# controller_v6.net
KiCad netlist of a schematic drawn in EAGLE
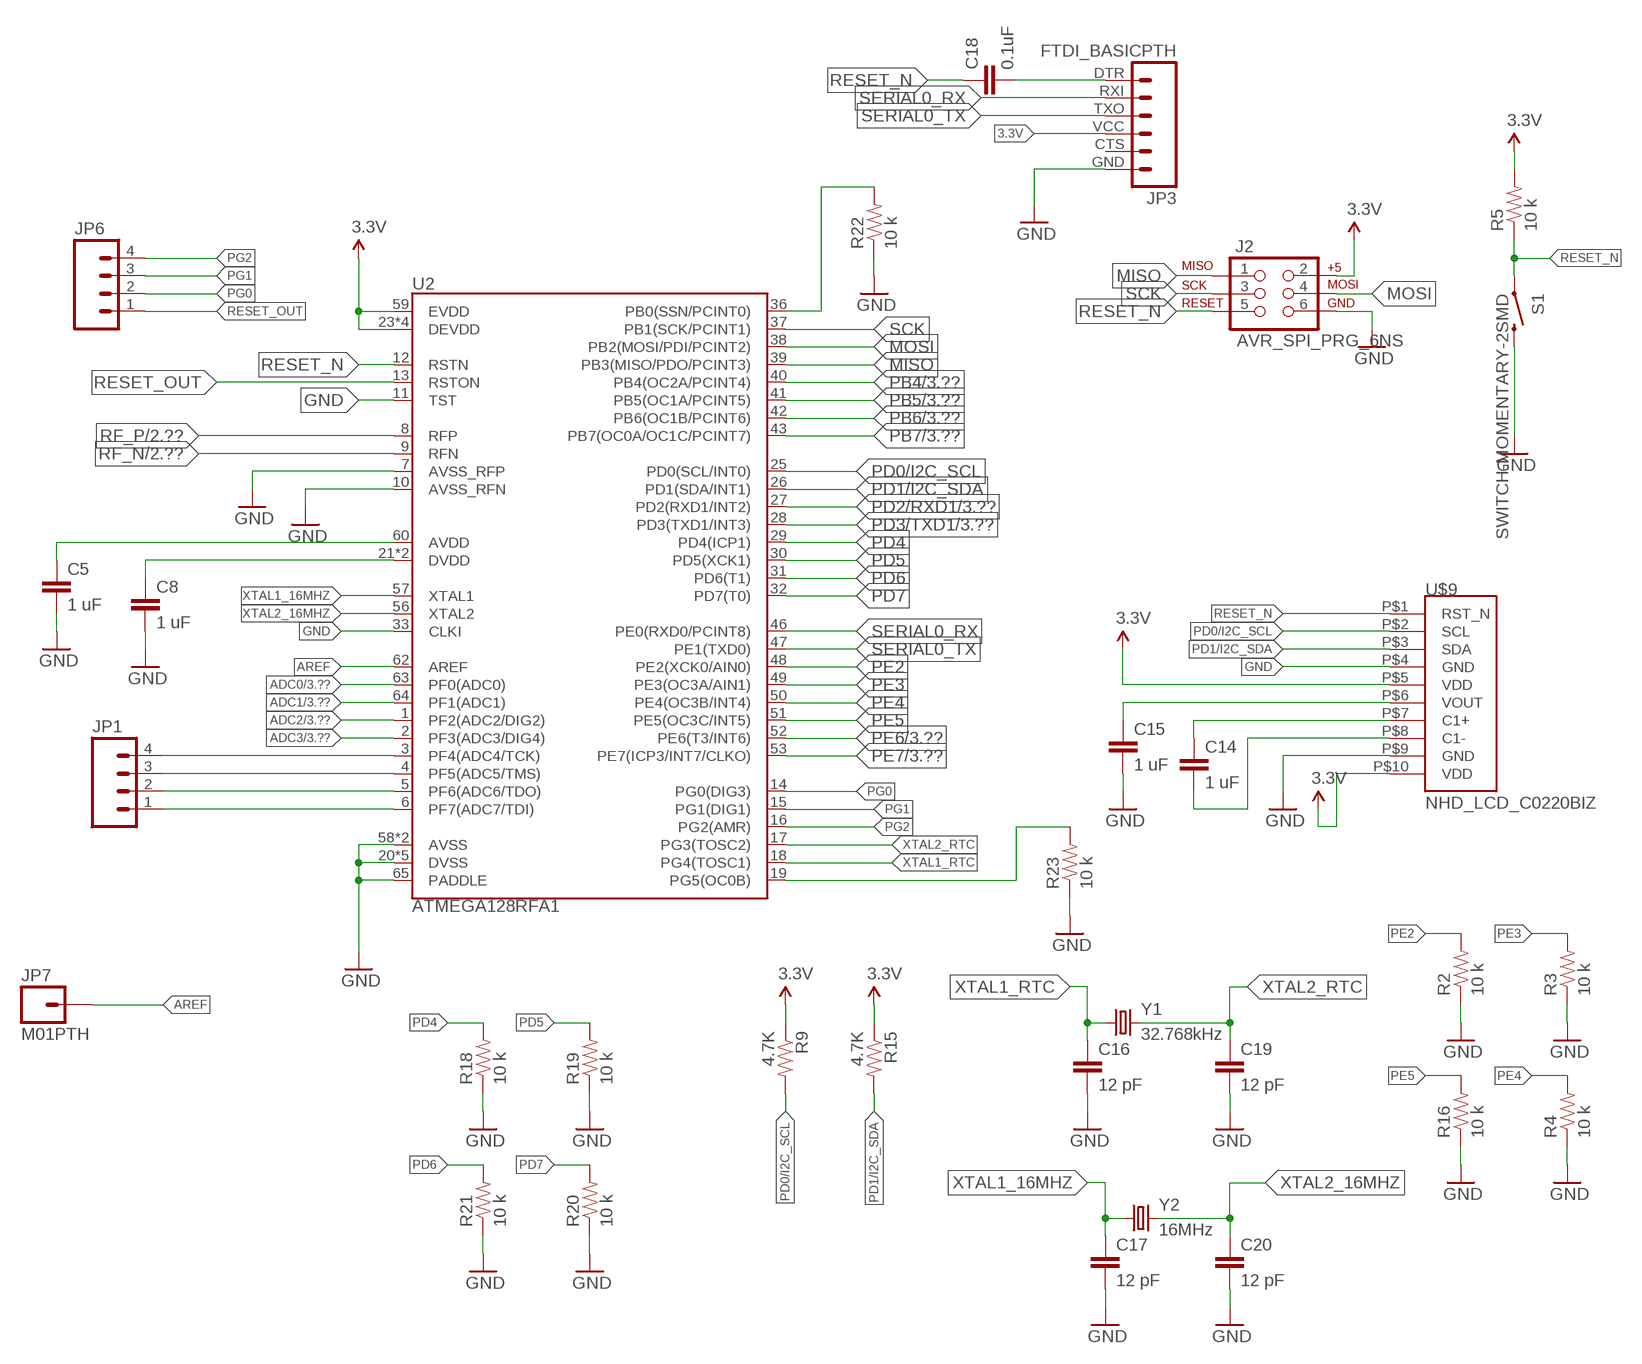
[diagram p0: schematic, sheet 1]
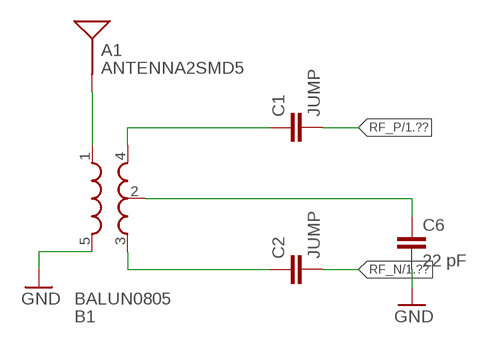
[diagram p1: schematic, sheet 2]
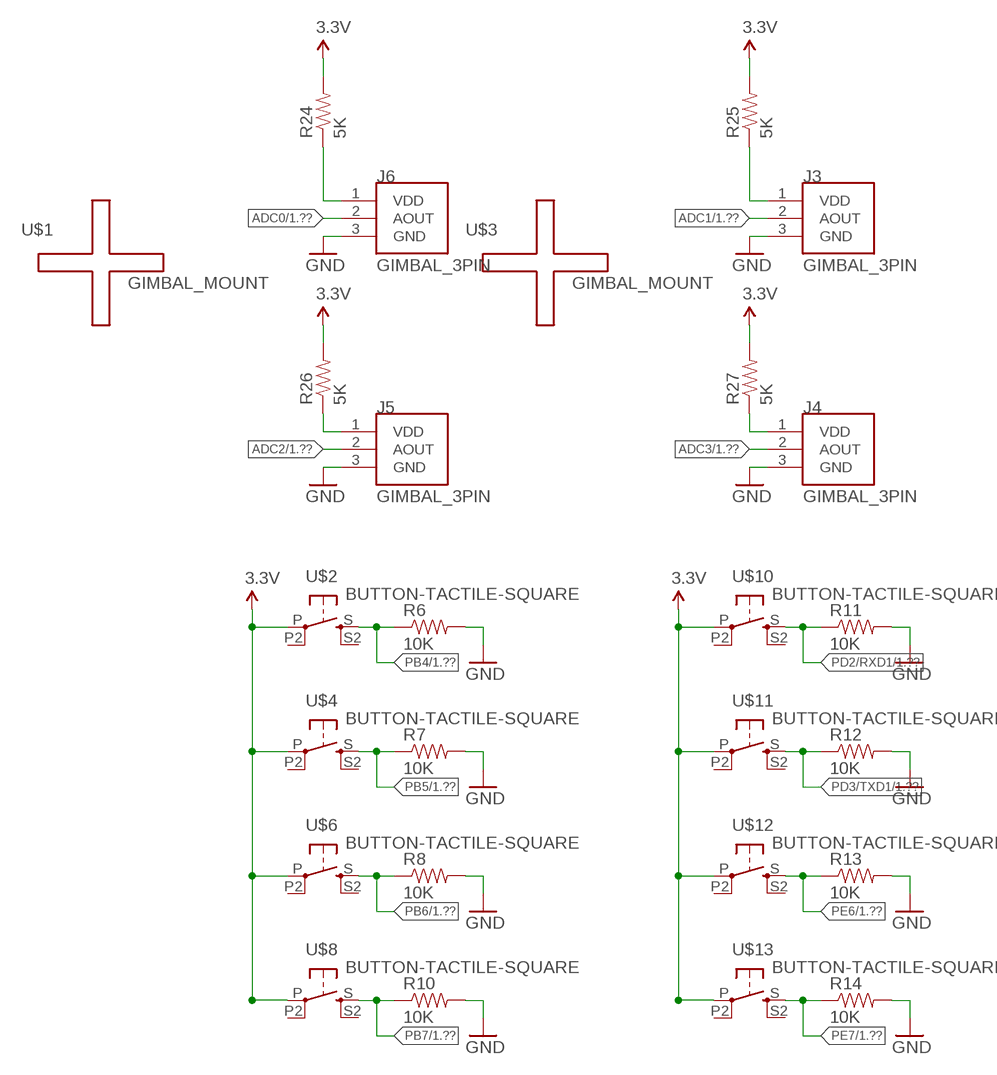
[diagram p2: schematic, sheet 3]
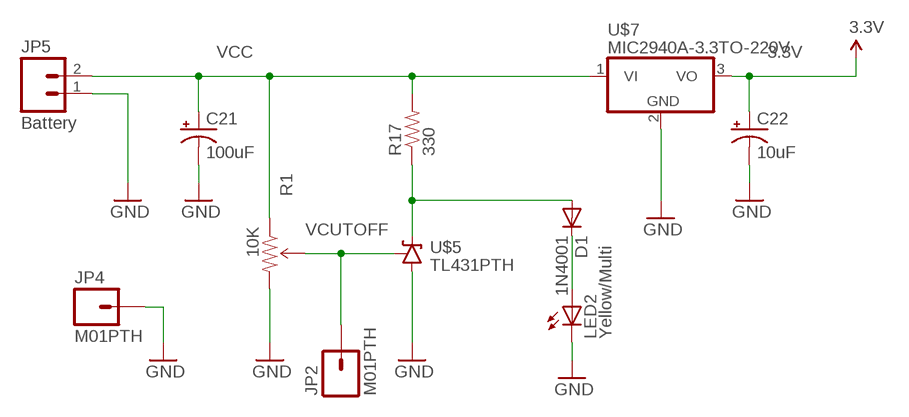
[diagram p3: schematic, sheet 4]

(export (version "E")
  (design (tool "Eeschema 10.0.6"))
  (components
    (comp (ref "C21")
      (value "100uF")
      (footprint "eagle-import:E3,5-8")
      (libsource (lib "eagle-import") (part "CPOL-USE3.5-8"))
    )
    (comp (ref "C22")
      (value "10uF")
      (footprint "eagle-import:E2,5-5")
      (libsource (lib "eagle-import") (part "CPOL-USE2.5-5"))
    )
    (comp (ref "D1")
      (value "1N4001")
      (footprint "eagle-import:DO41-10")
      (libsource (lib "eagle-import") (part "1N4004"))
    )
    (comp (ref "JP2")
      (value "M01PTH")
      (footprint "eagle-import:1X01")
      (libsource (lib "eagle-import") (part "SparkFun_M01PTH"))
    )
    (comp (ref "JP4")
      (value "M01PTH")
      (footprint "eagle-import:1X01")
      (libsource (lib "eagle-import") (part "SparkFun_M01PTH"))
    )
    (comp (ref "JP5")
      (value "Battery")
      (footprint "eagle-import:1X02")
      (libsource (lib "eagle-import") (part "M02PTH"))
    )
    (comp (ref "LED2")
      (value "Yellow/Multi")
      (footprint "eagle-import:LED5MM")
      (libsource (lib "eagle-import") (part "LED5MM"))
    )
    (comp (ref "R1")
      (value "10K")
      (footprint "eagle-import:3386U")
      (fields (field (name "CREATOR") "Brandon") (field (name "REVIEWER1") "Chris"))
      (libsource (lib "eagle-import") (part "TRIMPOT-PTH-KNOB"))
    )
    (comp (ref "R17")
      (value "330")
      (footprint "eagle-import:AXIAL-0.3")
      (libsource (lib "eagle-import") (part "SparkFun_RESISTORAXIAL-0.3"))
    )
    (comp (ref "U$5")
      (value "TL431PTH")
      (footprint "eagle-import:TO-92")
      (libsource (lib "eagle-import") (part "TL431PTH"))
    )
    (comp (ref "U$7")
      (value "MIC2940A-3.3TO-220V")
      (footprint "eagle-import:TO-220V")
      (libsource (lib "eagle-import") (part "MIC2940A-3.3TO-220V"))
    )
    (comp (ref "J3")
      (value "GIMBAL_3PIN")
      (footprint "eagle-import:JST-3-PTH")
      (libsource (lib "eagle-import") (part "GIMBAL_3PIN"))
    )
    (comp (ref "J4")
      (value "GIMBAL_3PIN")
      (footprint "eagle-import:JST-3-PTH")
      (libsource (lib "eagle-import") (part "GIMBAL_3PIN"))
    )
    (comp (ref "J5")
      (value "GIMBAL_3PIN")
      (footprint "eagle-import:JST-3-PTH")
      (libsource (lib "eagle-import") (part "GIMBAL_3PIN"))
    )
    (comp (ref "J6")
      (value "GIMBAL_3PIN")
      (footprint "eagle-import:JST-3-PTH")
      (libsource (lib "eagle-import") (part "GIMBAL_3PIN"))
    )
    (comp (ref "R6")
      (value "10K")
      (footprint "eagle-import:0805")
      (libsource (lib "eagle-import") (part "RESISTOR0805-RES"))
    )
    (comp (ref "R7")
      (value "10K")
      (footprint "eagle-import:0805")
      (libsource (lib "eagle-import") (part "RESISTOR0805-RES"))
    )
    (comp (ref "R8")
      (value "10K")
      (footprint "eagle-import:0805")
      (libsource (lib "eagle-import") (part "RESISTOR0805-RES"))
    )
    (comp (ref "R10")
      (value "10K")
      (footprint "eagle-import:0805")
      (libsource (lib "eagle-import") (part "RESISTOR0805-RES"))
    )
    (comp (ref "R11")
      (value "10K")
      (footprint "eagle-import:0805")
      (libsource (lib "eagle-import") (part "RESISTOR0805-RES"))
    )
    (comp (ref "R12")
      (value "10K")
      (footprint "eagle-import:0805")
      (libsource (lib "eagle-import") (part "RESISTOR0805-RES"))
    )
    (comp (ref "R13")
      (value "10K")
      (footprint "eagle-import:0805")
      (libsource (lib "eagle-import") (part "RESISTOR0805-RES"))
    )
    (comp (ref "R14")
      (value "10K")
      (footprint "eagle-import:0805")
      (libsource (lib "eagle-import") (part "RESISTOR0805-RES"))
    )
    (comp (ref "R24")
      (value "5K")
      (footprint "eagle-import:0805")
      (libsource (lib "eagle-import") (part "RESISTOR0805-RES"))
    )
    (comp (ref "R25")
      (value "5K")
      (footprint "eagle-import:0805")
      (libsource (lib "eagle-import") (part "RESISTOR0805-RES"))
    )
    (comp (ref "R26")
      (value "5K")
      (footprint "eagle-import:0805")
      (libsource (lib "eagle-import") (part "RESISTOR0805-RES"))
    )
    (comp (ref "R27")
      (value "5K")
      (footprint "eagle-import:0805")
      (libsource (lib "eagle-import") (part "RESISTOR0805-RES"))
    )
    (comp (ref "U$1")
      (value "GIMBAL_MOUNT")
      (footprint "eagle-import:GIMBAL_FOOTPRINT")
      (libsource (lib "eagle-import") (part "GIMBAL_MOUNT"))
    )
    (comp (ref "U$2")
      (value "BUTTON-TACTILE-SQUARE")
      (footprint "eagle-import:BUTTON-TACTILE-SQUARE-ADAFRUIT1010")
      (libsource (lib "eagle-import") (part "BUTTON-TACTILE-SQUARE"))
    )
    (comp (ref "U$3")
      (value "GIMBAL_MOUNT")
      (footprint "eagle-import:GIMBAL_FOOTPRINT")
      (libsource (lib "eagle-import") (part "GIMBAL_MOUNT"))
    )
    (comp (ref "U$4")
      (value "BUTTON-TACTILE-SQUARE")
      (footprint "eagle-import:BUTTON-TACTILE-SQUARE-ADAFRUIT1010")
      (libsource (lib "eagle-import") (part "BUTTON-TACTILE-SQUARE"))
    )
    (comp (ref "U$6")
      (value "BUTTON-TACTILE-SQUARE")
      (footprint "eagle-import:BUTTON-TACTILE-SQUARE-ADAFRUIT1010")
      (libsource (lib "eagle-import") (part "BUTTON-TACTILE-SQUARE"))
    )
    (comp (ref "U$8")
      (value "BUTTON-TACTILE-SQUARE")
      (footprint "eagle-import:BUTTON-TACTILE-SQUARE-ADAFRUIT1010")
      (libsource (lib "eagle-import") (part "BUTTON-TACTILE-SQUARE"))
    )
    (comp (ref "U$10")
      (value "BUTTON-TACTILE-SQUARE")
      (footprint "eagle-import:BUTTON-TACTILE-SQUARE-ADAFRUIT1010")
      (libsource (lib "eagle-import") (part "BUTTON-TACTILE-SQUARE"))
    )
    (comp (ref "U$11")
      (value "BUTTON-TACTILE-SQUARE")
      (footprint "eagle-import:BUTTON-TACTILE-SQUARE-ADAFRUIT1010")
      (libsource (lib "eagle-import") (part "BUTTON-TACTILE-SQUARE"))
    )
    (comp (ref "U$12")
      (value "BUTTON-TACTILE-SQUARE")
      (footprint "eagle-import:BUTTON-TACTILE-SQUARE-ADAFRUIT1010")
      (libsource (lib "eagle-import") (part "BUTTON-TACTILE-SQUARE"))
    )
    (comp (ref "U$13")
      (value "BUTTON-TACTILE-SQUARE")
      (footprint "eagle-import:BUTTON-TACTILE-SQUARE-ADAFRUIT1010")
      (libsource (lib "eagle-import") (part "BUTTON-TACTILE-SQUARE"))
    )
    (comp (ref "A1")
      (value "ANTENNA2SMD5")
      (footprint "eagle-import:ANTENNA-CHIP5")
      (libsource (lib "eagle-import") (part "ANTENNA2SMD5"))
    )
    (comp (ref "B1")
      (value "BALUN0805")
      (footprint "eagle-import:BALUN")
      (libsource (lib "eagle-import") (part "BALUN0805"))
    )
    (comp (ref "C1")
      (value "JUMP")
      (footprint "eagle-import:0805")
      (libsource (lib "eagle-import") (part "CAP0805"))
    )
    (comp (ref "C2")
      (value "JUMP")
      (footprint "eagle-import:0805")
      (libsource (lib "eagle-import") (part "CAP0805"))
    )
    (comp (ref "C6")
      (value "22 pF")
      (footprint "eagle-import:0805")
      (libsource (lib "eagle-import") (part "CAP0805"))
    )
    (comp (ref "C5")
      (value "1 uF")
      (footprint "eagle-import:0805")
      (libsource (lib "eagle-import") (part "CAP0805"))
    )
    (comp (ref "C8")
      (value "1 uF")
      (footprint "eagle-import:0805")
      (libsource (lib "eagle-import") (part "CAP0805"))
    )
    (comp (ref "C14")
      (value "1 uF")
      (footprint "eagle-import:0805")
      (libsource (lib "eagle-import") (part "CAP0805"))
    )
    (comp (ref "C15")
      (value "1 uF")
      (footprint "eagle-import:0805")
      (libsource (lib "eagle-import") (part "CAP0805"))
    )
    (comp (ref "C16")
      (value "12 pF")
      (footprint "eagle-import:0805")
      (libsource (lib "eagle-import") (part "CAP0805"))
    )
    (comp (ref "C17")
      (value "12 pF")
      (footprint "eagle-import:0805")
      (libsource (lib "eagle-import") (part "CAP0805"))
    )
    (comp (ref "C18")
      (value "0.1uF")
      (footprint "eagle-import:0805")
      (libsource (lib "eagle-import") (part "CAP0805"))
    )
    (comp (ref "C19")
      (value "12 pF")
      (footprint "eagle-import:0805")
      (libsource (lib "eagle-import") (part "CAP0805"))
    )
    (comp (ref "C20")
      (value "12 pF")
      (footprint "eagle-import:0805")
      (libsource (lib "eagle-import") (part "CAP0805"))
    )
    (comp (ref "J2")
      (value "AVR_SPI_PRG_6NS")
      (footprint "eagle-import:2X3-NS")
      (libsource (lib "eagle-import") (part "AVR_SPI_PRG_6NS"))
    )
    (comp (ref "JP1")
      (value "M04PTH")
      (footprint "eagle-import:1X04")
      (libsource (lib "eagle-import") (part "M04PTH"))
    )
    (comp (ref "JP3")
      (value "FTDI_BASICPTH")
      (footprint "eagle-import:FTDI_BASIC")
      (libsource (lib "eagle-import") (part "FTDI_BASICPTH"))
    )
    (comp (ref "JP6")
      (value "M04PTH")
      (footprint "eagle-import:1X04")
      (libsource (lib "eagle-import") (part "M04PTH"))
    )
    (comp (ref "JP7")
      (value "M01PTH")
      (footprint "eagle-import:1X01")
      (libsource (lib "eagle-import") (part "M01PTH"))
    )
    (comp (ref "R2")
      (value "10 k")
      (footprint "eagle-import:0805")
      (libsource (lib "eagle-import") (part "RESISTOR0805-RES"))
    )
    (comp (ref "R3")
      (value "10 k")
      (footprint "eagle-import:0805")
      (libsource (lib "eagle-import") (part "RESISTOR0805-RES"))
    )
    (comp (ref "R4")
      (value "10 k")
      (footprint "eagle-import:0805")
      (libsource (lib "eagle-import") (part "RESISTOR0805-RES"))
    )
    (comp (ref "R5")
      (value "10 k")
      (footprint "eagle-import:0805")
      (libsource (lib "eagle-import") (part "RESISTOR0805-RES"))
    )
    (comp (ref "R9")
      (value "4.7K")
      (footprint "eagle-import:0805")
      (libsource (lib "eagle-import") (part "RESISTOR0805-RES"))
    )
    (comp (ref "R15")
      (value "4.7K")
      (footprint "eagle-import:0805")
      (libsource (lib "eagle-import") (part "RESISTOR0805-RES"))
    )
    (comp (ref "R16")
      (value "10 k")
      (footprint "eagle-import:0805")
      (libsource (lib "eagle-import") (part "RESISTOR0805-RES"))
    )
    (comp (ref "R18")
      (value "10 k")
      (footprint "eagle-import:0805")
      (libsource (lib "eagle-import") (part "RESISTOR0805-RES"))
    )
    (comp (ref "R19")
      (value "10 k")
      (footprint "eagle-import:0805")
      (libsource (lib "eagle-import") (part "RESISTOR0805-RES"))
    )
    (comp (ref "R20")
      (value "10 k")
      (footprint "eagle-import:0805")
      (libsource (lib "eagle-import") (part "RESISTOR0805-RES"))
    )
    (comp (ref "R21")
      (value "10 k")
      (footprint "eagle-import:0805")
      (libsource (lib "eagle-import") (part "RESISTOR0805-RES"))
    )
    (comp (ref "R22")
      (value "10 k")
      (footprint "eagle-import:0805")
      (libsource (lib "eagle-import") (part "RESISTOR0805-RES"))
    )
    (comp (ref "R23")
      (value "10 k")
      (footprint "eagle-import:0805")
      (libsource (lib "eagle-import") (part "RESISTOR0805-RES"))
    )
    (comp (ref "S1")
      (value "SWITCH-MOMENTARY-2SMD")
      (footprint "eagle-import:TACTILE_SWITCH_SMD")
      (libsource (lib "eagle-import") (part "SWITCH-MOMENTARY-2SMD"))
    )
    (comp (ref "U$9")
      (value "NHD_LCD_C0220BIZ")
      (footprint "eagle-import:1X08-2MMPTH-LCD")
      (libsource (lib "eagle-import") (part "NHD_LCD_C0220BIZ"))
    )
    (comp (ref "U2")
      (value "ATMEGA128RFA1")
      (footprint "eagle-import:QFN-64")
      (libsource (lib "eagle-import") (part "ATMEGA128RFA1"))
    )
    (comp (ref "Y1")
      (value "32.768kHz")
      (footprint "eagle-import:CRYSTAL-32KHZ-SMD")
      (libsource (lib "eagle-import") (part "CRYSTAL32-SMD"))
    )
    (comp (ref "Y2")
      (value "16MHz")
      (footprint "eagle-import:CRYSTAL-SMD-5X3")
      (libsource (lib "eagle-import") (part "CRYSTAL5X3"))
    )
  )
  (nets
    (net (code "1") (name "3.3V") (class "Default")
      (node (ref "C22") (pin "+") (pinfunction "+_+") (pintype "passive"))
      (node (ref "J2") (pin "2") (pinfunction "2_2") (pintype "passive"))
      (node (ref "JP3") (pin "VCC") (pinfunction "4_VCC") (pintype "passive"))
      (node (ref "R15") (pin "1") (pinfunction "1_1") (pintype "passive"))
      (node (ref "R24") (pin "2") (pinfunction "2_2") (pintype "passive"))
      (node (ref "R25") (pin "2") (pinfunction "2_2") (pintype "passive"))
      (node (ref "R26") (pin "2") (pinfunction "2_2") (pintype "passive"))
      (node (ref "R27") (pin "2") (pinfunction "2_2") (pintype "passive"))
      (node (ref "R5") (pin "2") (pinfunction "2_2") (pintype "passive"))
      (node (ref "R9") (pin "1") (pinfunction "1_1") (pintype "passive"))
      (node (ref "U$10") (pin "P") (pinfunction "P_P") (pintype "passive"))
      (node (ref "U$11") (pin "P") (pinfunction "P_P") (pintype "passive"))
      (node (ref "U$12") (pin "P") (pinfunction "P_P") (pintype "passive"))
      (node (ref "U$13") (pin "P") (pinfunction "P_P") (pintype "passive"))
      (node (ref "U$2") (pin "P") (pinfunction "P_P") (pintype "passive"))
      (node (ref "U$4") (pin "P") (pinfunction "P_P") (pintype "passive"))
      (node (ref "U$6") (pin "P") (pinfunction "P_P") (pintype "passive"))
      (node (ref "U$7") (pin "3") (pinfunction "VO_3") (pintype "passive"))
      (node (ref "U$8") (pin "P") (pinfunction "P_P") (pintype "passive"))
      (node (ref "U$9") (pin "P$10") (pinfunction "VDD_P$10") (pintype "bidirectional"))
      (node (ref "U$9") (pin "P$5") (pinfunction "VDD_P$5") (pintype "bidirectional"))
      (node (ref "U2") (pin "23") (pinfunction "DEVDD_23") (pintype "bidirectional"))
      (node (ref "U2") (pin "34") (pinfunction "DEVDD_34") (pintype "bidirectional"))
      (node (ref "U2") (pin "44") (pinfunction "DEVDD_44") (pintype "bidirectional"))
      (node (ref "U2") (pin "54") (pinfunction "DEVDD_54") (pintype "bidirectional"))
      (node (ref "U2") (pin "59") (pinfunction "EVDD_59") (pintype "bidirectional"))
    )
    (net (code "2") (name "ADC0") (class "Default")
      (node (ref "J6") (pin "2") (pinfunction "AOUT_2") (pintype "bidirectional"))
      (node (ref "U2") (pin "63") (pinfunction "PF0(ADC0)_63") (pintype "bidirectional"))
    )
    (net (code "3") (name "ADC1") (class "Default")
      (node (ref "J3") (pin "2") (pinfunction "AOUT_2") (pintype "bidirectional"))
      (node (ref "U2") (pin "64") (pinfunction "PF1(ADC1)_64") (pintype "bidirectional"))
    )
    (net (code "4") (name "ADC2") (class "Default")
      (node (ref "J5") (pin "2") (pinfunction "AOUT_2") (pintype "bidirectional"))
      (node (ref "U2") (pin "1") (pinfunction "PF2(ADC2/DIG2)_1") (pintype "bidirectional"))
    )
    (net (code "5") (name "ADC3") (class "Default")
      (node (ref "J4") (pin "2") (pinfunction "AOUT_2") (pintype "bidirectional"))
      (node (ref "U2") (pin "2") (pinfunction "PF3(ADC3/DIG4)_2") (pintype "bidirectional"))
    )
    (net (code "6") (name "AREF") (class "Default")
      (node (ref "JP7") (pin "1") (pinfunction "1_1") (pintype "passive"))
      (node (ref "U2") (pin "62") (pinfunction "AREF_62") (pintype "bidirectional"))
    )
    (net (code "7") (name "GND") (class "Default")
      (node (ref "B1") (pin "5") (pinfunction "GND_5") (pintype "bidirectional"))
      (node (ref "C15") (pin "2") (pinfunction "2_2") (pintype "passive"))
      (node (ref "C16") (pin "2") (pinfunction "2_2") (pintype "passive"))
      (node (ref "C17") (pin "2") (pinfunction "2_2") (pintype "passive"))
      (node (ref "C19") (pin "2") (pinfunction "2_2") (pintype "passive"))
      (node (ref "C20") (pin "2") (pinfunction "2_2") (pintype "passive"))
      (node (ref "C21") (pin "-") (pinfunction "-_-") (pintype "passive"))
      (node (ref "C22") (pin "-") (pinfunction "-_-") (pintype "passive"))
      (node (ref "C5") (pin "2") (pinfunction "2_2") (pintype "passive"))
      (node (ref "C6") (pin "2") (pinfunction "2_2") (pintype "passive"))
      (node (ref "C8") (pin "2") (pinfunction "2_2") (pintype "passive"))
      (node (ref "J2") (pin "6") (pinfunction "6_6") (pintype "passive"))
      (node (ref "J3") (pin "3") (pinfunction "GND_3") (pintype "power_in"))
      (node (ref "J4") (pin "3") (pinfunction "GND_3") (pintype "power_in"))
      (node (ref "J5") (pin "3") (pinfunction "GND_3") (pintype "power_in"))
      (node (ref "J6") (pin "3") (pinfunction "GND_3") (pintype "power_in"))
      (node (ref "JP3") (pin "GND") (pinfunction "6_GND") (pintype "passive"))
      (node (ref "JP4") (pin "1") (pinfunction "1_1") (pintype "passive"))
      (node (ref "JP5") (pin "1") (pinfunction "1_1") (pintype "passive"))
      (node (ref "LED2") (pin "K") (pinfunction "C_K") (pintype "passive"))
      (node (ref "R1") (pin "3") (pinfunction "CW_3") (pintype "passive"))
      (node (ref "R10") (pin "2") (pinfunction "2_2") (pintype "passive"))
      (node (ref "R11") (pin "2") (pinfunction "2_2") (pintype "passive"))
      (node (ref "R12") (pin "2") (pinfunction "2_2") (pintype "passive"))
      (node (ref "R13") (pin "2") (pinfunction "2_2") (pintype "passive"))
      (node (ref "R14") (pin "2") (pinfunction "2_2") (pintype "passive"))
      (node (ref "R16") (pin "1") (pinfunction "1_1") (pintype "passive"))
      (node (ref "R18") (pin "1") (pinfunction "1_1") (pintype "passive"))
      (node (ref "R19") (pin "1") (pinfunction "1_1") (pintype "passive"))
      (node (ref "R2") (pin "1") (pinfunction "1_1") (pintype "passive"))
      (node (ref "R20") (pin "1") (pinfunction "1_1") (pintype "passive"))
      (node (ref "R21") (pin "1") (pinfunction "1_1") (pintype "passive"))
      (node (ref "R22") (pin "1") (pinfunction "1_1") (pintype "passive"))
      (node (ref "R23") (pin "1") (pinfunction "1_1") (pintype "passive"))
      (node (ref "R3") (pin "1") (pinfunction "1_1") (pintype "passive"))
      (node (ref "R4") (pin "1") (pinfunction "1_1") (pintype "passive"))
      (node (ref "R6") (pin "2") (pinfunction "2_2") (pintype "passive"))
      (node (ref "R7") (pin "2") (pinfunction "2_2") (pintype "passive"))
      (node (ref "R8") (pin "2") (pinfunction "2_2") (pintype "passive"))
      (node (ref "S1") (pin "3") (pinfunction "2_3") (pintype "passive"))
      (node (ref "U$5") (pin "2") (pinfunction "A_2") (pintype "passive"))
      (node (ref "U$7") (pin "2") (pinfunction "GND_2") (pintype "passive"))
      (node (ref "U$9") (pin "P$4") (pinfunction "GND_P$4") (pintype "bidirectional"))
      (node (ref "U$9") (pin "P$9") (pinfunction "GND_P$9") (pintype "bidirectional"))
      (node (ref "U2") (pin "10") (pinfunction "AVSS_RFN_10") (pintype "bidirectional"))
      (node (ref "U2") (pin "11") (pinfunction "TST_11") (pintype "bidirectional"))
      (node (ref "U2") (pin "20") (pinfunction "DVSS_20") (pintype "bidirectional"))
      (node (ref "U2") (pin "24") (pinfunction "DVSS_24") (pintype "bidirectional"))
      (node (ref "U2") (pin "33") (pinfunction "CLKI_33") (pintype "bidirectional"))
      (node (ref "U2") (pin "35") (pinfunction "DVSS_35") (pintype "bidirectional"))
      (node (ref "U2") (pin "45") (pinfunction "DVSS_45") (pintype "bidirectional"))
      (node (ref "U2") (pin "55") (pinfunction "DVSS_55") (pintype "bidirectional"))
      (node (ref "U2") (pin "58") (pinfunction "AVSS_58") (pintype "bidirectional"))
      (node (ref "U2") (pin "61") (pinfunction "AVSS_61") (pintype "bidirectional"))
      (node (ref "U2") (pin "65") (pinfunction "PADDLE_65") (pintype "bidirectional"))
      (node (ref "U2") (pin "7") (pinfunction "AVSS_RFP_7") (pintype "bidirectional"))
    )
    (net (code "8") (name "MISO") (class "Default")
      (node (ref "J2") (pin "1") (pinfunction "1_1") (pintype "passive"))
      (node (ref "U2") (pin "39") (pinfunction "PB3(MISO/PDO/PCINT3)_39") (pintype "bidirectional"))
    )
    (net (code "9") (name "MOSI") (class "Default")
      (node (ref "J2") (pin "4") (pinfunction "4_4") (pintype "passive"))
      (node (ref "U2") (pin "38") (pinfunction "PB2(MOSI/PDI/PCINT2)_38") (pintype "bidirectional"))
    )
    (net (code "10") (name "Net-(A1-SIGNAL)") (class "Default")
      (node (ref "A1") (pin "FEED") (pinfunction "SIGNAL_FEED") (pintype "bidirectional"))
      (node (ref "B1") (pin "1") (pinfunction "IN_1") (pintype "bidirectional"))
    )
    (net (code "11") (name "Net-(B1-GND-Pad2)") (class "Default")
      (node (ref "B1") (pin "2") (pinfunction "GND_2") (pintype "bidirectional"))
      (node (ref "C6") (pin "1") (pinfunction "1_1") (pintype "passive"))
    )
    (net (code "12") (name "Net-(B1-OUT1)") (class "Default")
      (node (ref "B1") (pin "4") (pinfunction "OUT1_4") (pintype "bidirectional"))
      (node (ref "C1") (pin "1") (pinfunction "1_1") (pintype "passive"))
    )
    (net (code "13") (name "Net-(B1-OUT2)") (class "Default")
      (node (ref "B1") (pin "3") (pinfunction "OUT2_3") (pintype "bidirectional"))
      (node (ref "C2") (pin "1") (pinfunction "1_1") (pintype "passive"))
    )
    (net (code "14") (name "Net-(C8-Pad1)") (class "Default")
      (node (ref "C8") (pin "1") (pinfunction "1_1") (pintype "passive"))
      (node (ref "U2") (pin "21") (pinfunction "DVDD_21") (pintype "bidirectional"))
      (node (ref "U2") (pin "22") (pinfunction "DVDD_22") (pintype "bidirectional"))
    )
    (net (code "15") (name "Net-(D1-PadC)") (class "Default")
      (node (ref "D1") (pin "C") (pinfunction "C_C") (pintype "passive"))
      (node (ref "LED2") (pin "A") (pinfunction "A_A") (pintype "passive"))
    )
    (net (code "16") (name "Net-(J3-VDD)") (class "Default")
      (node (ref "J3") (pin "1") (pinfunction "VDD_1") (pintype "power_in"))
      (node (ref "R25") (pin "1") (pinfunction "1_1") (pintype "passive"))
    )
    (net (code "17") (name "Net-(J4-VDD)") (class "Default")
      (node (ref "J4") (pin "1") (pinfunction "VDD_1") (pintype "power_in"))
      (node (ref "R27") (pin "1") (pinfunction "1_1") (pintype "passive"))
    )
    (net (code "18") (name "Net-(J5-VDD)") (class "Default")
      (node (ref "J5") (pin "1") (pinfunction "VDD_1") (pintype "power_in"))
      (node (ref "R26") (pin "1") (pinfunction "1_1") (pintype "passive"))
    )
    (net (code "19") (name "Net-(J6-VDD)") (class "Default")
      (node (ref "J6") (pin "1") (pinfunction "VDD_1") (pintype "power_in"))
      (node (ref "R24") (pin "1") (pinfunction "1_1") (pintype "passive"))
    )
    (net (code "20") (name "Net-(JP3-1)") (class "Default")
      (node (ref "C18") (pin "2") (pinfunction "2_2") (pintype "passive"))
      (node (ref "JP3") (pin "DTR") (pinfunction "1_DTR") (pintype "passive"))
    )
    (net (code "21") (name "Net-(R17-1)") (class "Default")
      (node (ref "D1") (pin "A") (pinfunction "A_A") (pintype "passive"))
      (node (ref "R17") (pin "P$1") (pinfunction "1_P$1") (pintype "passive"))
      (node (ref "U$5") (pin "3") (pinfunction "C_3") (pintype "passive"))
    )
    (net (code "22") (name "Net-(U$9-C1+)") (class "Default")
      (node (ref "C14") (pin "1") (pinfunction "1_1") (pintype "passive"))
      (node (ref "U$9") (pin "P$7") (pinfunction "C1+_P$7") (pintype "bidirectional"))
    )
    (net (code "23") (name "Net-(U$9-C1-)") (class "Default")
      (node (ref "C14") (pin "2") (pinfunction "2_2") (pintype "passive"))
      (node (ref "U$9") (pin "P$8") (pinfunction "C1-_P$8") (pintype "bidirectional"))
    )
    (net (code "24") (name "Net-(U$9-VOUT)") (class "Default")
      (node (ref "C15") (pin "1") (pinfunction "1_1") (pintype "passive"))
      (node (ref "U$9") (pin "P$6") (pinfunction "VOUT_P$6") (pintype "bidirectional"))
    )
    (net (code "25") (name "Net-(U2-AVDD)") (class "Default")
      (node (ref "C5") (pin "1") (pinfunction "1_1") (pintype "passive"))
      (node (ref "U2") (pin "60") (pinfunction "AVDD_60") (pintype "bidirectional"))
    )
    (net (code "26") (name "Net-(U2-PB0(SSN{slash}PCINT0))") (class "Default")
      (node (ref "R22") (pin "2") (pinfunction "2_2") (pintype "passive"))
      (node (ref "U2") (pin "36") (pinfunction "PB0(SSN/PCINT0)_36") (pintype "bidirectional"))
    )
    (net (code "27") (name "Net-(U2-PF4(ADC4{slash}TCK))") (class "Default")
      (node (ref "JP1") (pin "4") (pinfunction "4_4") (pintype "passive"))
      (node (ref "U2") (pin "3") (pinfunction "PF4(ADC4/TCK)_3") (pintype "bidirectional"))
    )
    (net (code "28") (name "Net-(U2-PF5(ADC5{slash}TMS))") (class "Default")
      (node (ref "JP1") (pin "3") (pinfunction "3_3") (pintype "passive"))
      (node (ref "U2") (pin "4") (pinfunction "PF5(ADC5/TMS)_4") (pintype "bidirectional"))
    )
    (net (code "29") (name "Net-(U2-PF6(ADC6{slash}TDO))") (class "Default")
      (node (ref "JP1") (pin "2") (pinfunction "2_2") (pintype "passive"))
      (node (ref "U2") (pin "5") (pinfunction "PF6(ADC6/TDO)_5") (pintype "bidirectional"))
    )
    (net (code "30") (name "Net-(U2-PF7(ADC7{slash}TDI))") (class "Default")
      (node (ref "JP1") (pin "1") (pinfunction "1_1") (pintype "passive"))
      (node (ref "U2") (pin "6") (pinfunction "PF7(ADC7/TDI)_6") (pintype "bidirectional"))
    )
    (net (code "31") (name "Net-(U2-PG5(OC0B))") (class "Default")
      (node (ref "R23") (pin "2") (pinfunction "2_2") (pintype "passive"))
      (node (ref "U2") (pin "19") (pinfunction "PG5(OC0B)_19") (pintype "bidirectional"))
    )
    (net (code "32") (name "PB4") (class "Default")
      (node (ref "R6") (pin "1") (pinfunction "1_1") (pintype "passive"))
      (node (ref "U$2") (pin "S") (pinfunction "S_S") (pintype "passive"))
      (node (ref "U2") (pin "40") (pinfunction "PB4(OC2A/PCINT4)_40") (pintype "bidirectional"))
    )
    (net (code "33") (name "PB5") (class "Default")
      (node (ref "R7") (pin "1") (pinfunction "1_1") (pintype "passive"))
      (node (ref "U$4") (pin "S") (pinfunction "S_S") (pintype "passive"))
      (node (ref "U2") (pin "41") (pinfunction "PB5(OC1A/PCINT5)_41") (pintype "bidirectional"))
    )
    (net (code "34") (name "PB6") (class "Default")
      (node (ref "R8") (pin "1") (pinfunction "1_1") (pintype "passive"))
      (node (ref "U$6") (pin "S") (pinfunction "S_S") (pintype "passive"))
      (node (ref "U2") (pin "42") (pinfunction "PB6(OC1B/PCINT6)_42") (pintype "bidirectional"))
    )
    (net (code "35") (name "PB7") (class "Default")
      (node (ref "R10") (pin "1") (pinfunction "1_1") (pintype "passive"))
      (node (ref "U$8") (pin "S") (pinfunction "S_S") (pintype "passive"))
      (node (ref "U2") (pin "43") (pinfunction "PB7(OC0A/OC1C/PCINT7)_43") (pintype "bidirectional"))
    )
    (net (code "36") (name "PD0{slash}I2C_SCL") (class "Default")
      (node (ref "R9") (pin "2") (pinfunction "2_2") (pintype "passive"))
      (node (ref "U$9") (pin "P$2") (pinfunction "SCL_P$2") (pintype "bidirectional"))
      (node (ref "U2") (pin "25") (pinfunction "PD0(SCL/INT0)_25") (pintype "bidirectional"))
    )
    (net (code "37") (name "PD1{slash}I2C_SDA") (class "Default")
      (node (ref "R15") (pin "2") (pinfunction "2_2") (pintype "passive"))
      (node (ref "U$9") (pin "P$3") (pinfunction "SDA_P$3") (pintype "bidirectional"))
      (node (ref "U2") (pin "26") (pinfunction "PD1(SDA/INT1)_26") (pintype "bidirectional"))
    )
    (net (code "38") (name "PD2{slash}RXD1") (class "Default")
      (node (ref "R11") (pin "1") (pinfunction "1_1") (pintype "passive"))
      (node (ref "U$10") (pin "S") (pinfunction "S_S") (pintype "passive"))
      (node (ref "U2") (pin "27") (pinfunction "PD2(RXD1/INT2)_27") (pintype "bidirectional"))
    )
    (net (code "39") (name "PD3{slash}TXD1") (class "Default")
      (node (ref "R12") (pin "1") (pinfunction "1_1") (pintype "passive"))
      (node (ref "U$11") (pin "S") (pinfunction "S_S") (pintype "passive"))
      (node (ref "U2") (pin "28") (pinfunction "PD3(TXD1/INT3)_28") (pintype "bidirectional"))
    )
    (net (code "40") (name "PD4") (class "Default")
      (node (ref "R18") (pin "2") (pinfunction "2_2") (pintype "passive"))
      (node (ref "U2") (pin "29") (pinfunction "PD4(ICP1)_29") (pintype "bidirectional"))
    )
    (net (code "41") (name "PD5") (class "Default")
      (node (ref "R19") (pin "2") (pinfunction "2_2") (pintype "passive"))
      (node (ref "U2") (pin "30") (pinfunction "PD5(XCK1)_30") (pintype "bidirectional"))
    )
    (net (code "42") (name "PD6") (class "Default")
      (node (ref "R21") (pin "2") (pinfunction "2_2") (pintype "passive"))
      (node (ref "U2") (pin "31") (pinfunction "PD6(T1)_31") (pintype "bidirectional"))
    )
    (net (code "43") (name "PD7") (class "Default")
      (node (ref "R20") (pin "2") (pinfunction "2_2") (pintype "passive"))
      (node (ref "U2") (pin "32") (pinfunction "PD7(T0)_32") (pintype "bidirectional"))
    )
    (net (code "44") (name "PE2") (class "Default")
      (node (ref "R2") (pin "2") (pinfunction "2_2") (pintype "passive"))
      (node (ref "U2") (pin "48") (pinfunction "PE2(XCK0/AIN0)_48") (pintype "bidirectional"))
    )
    (net (code "45") (name "PE3") (class "Default")
      (node (ref "R3") (pin "2") (pinfunction "2_2") (pintype "passive"))
      (node (ref "U2") (pin "49") (pinfunction "PE3(OC3A/AIN1)_49") (pintype "bidirectional"))
    )
    (net (code "46") (name "PE4") (class "Default")
      (node (ref "R4") (pin "2") (pinfunction "2_2") (pintype "passive"))
      (node (ref "U2") (pin "50") (pinfunction "PE4(OC3B/INT4)_50") (pintype "bidirectional"))
    )
    (net (code "47") (name "PE5") (class "Default")
      (node (ref "R16") (pin "2") (pinfunction "2_2") (pintype "passive"))
      (node (ref "U2") (pin "51") (pinfunction "PE5(OC3C/INT5)_51") (pintype "bidirectional"))
    )
    (net (code "48") (name "PE6") (class "Default")
      (node (ref "R13") (pin "1") (pinfunction "1_1") (pintype "passive"))
      (node (ref "U$12") (pin "S") (pinfunction "S_S") (pintype "passive"))
      (node (ref "U2") (pin "52") (pinfunction "PE6(T3/INT6)_52") (pintype "bidirectional"))
    )
    (net (code "49") (name "PE7") (class "Default")
      (node (ref "R14") (pin "1") (pinfunction "1_1") (pintype "passive"))
      (node (ref "U$13") (pin "S") (pinfunction "S_S") (pintype "passive"))
      (node (ref "U2") (pin "53") (pinfunction "PE7(ICP3/INT7/CLKO)_53") (pintype "bidirectional"))
    )
    (net (code "50") (name "PG0") (class "Default")
      (node (ref "JP6") (pin "2") (pinfunction "2_2") (pintype "passive"))
      (node (ref "U2") (pin "14") (pinfunction "PG0(DIG3)_14") (pintype "bidirectional"))
    )
    (net (code "51") (name "PG1") (class "Default")
      (node (ref "JP6") (pin "3") (pinfunction "3_3") (pintype "passive"))
      (node (ref "U2") (pin "15") (pinfunction "PG1(DIG1)_15") (pintype "bidirectional"))
    )
    (net (code "52") (name "PG2") (class "Default")
      (node (ref "JP6") (pin "4") (pinfunction "4_4") (pintype "passive"))
      (node (ref "U2") (pin "16") (pinfunction "PG2(AMR)_16") (pintype "bidirectional"))
    )
    (net (code "53") (name "RESET_N") (class "Default")
      (node (ref "C18") (pin "1") (pinfunction "1_1") (pintype "passive"))
      (node (ref "J2") (pin "5") (pinfunction "5_5") (pintype "passive"))
      (node (ref "R5") (pin "1") (pinfunction "1_1") (pintype "passive"))
      (node (ref "S1") (pin "1") (pinfunction "1_1") (pintype "passive"))
      (node (ref "U$9") (pin "P$1") (pinfunction "RST_N_P$1") (pintype "bidirectional"))
      (node (ref "U2") (pin "12") (pinfunction "RSTN_12") (pintype "bidirectional"))
    )
    (net (code "54") (name "RESET_OUT") (class "Default")
      (node (ref "JP6") (pin "1") (pinfunction "1_1") (pintype "passive"))
      (node (ref "U2") (pin "13") (pinfunction "RSTON_13") (pintype "bidirectional"))
    )
    (net (code "55") (name "RF_N") (class "Default")
      (node (ref "C2") (pin "2") (pinfunction "2_2") (pintype "passive"))
      (node (ref "U2") (pin "9") (pinfunction "RFN_9") (pintype "bidirectional"))
    )
    (net (code "56") (name "RF_P") (class "Default")
      (node (ref "C1") (pin "2") (pinfunction "2_2") (pintype "passive"))
      (node (ref "U2") (pin "8") (pinfunction "RFP_8") (pintype "bidirectional"))
    )
    (net (code "57") (name "SCK") (class "Default")
      (node (ref "J2") (pin "3") (pinfunction "3_3") (pintype "passive"))
      (node (ref "U2") (pin "37") (pinfunction "PB1(SCK/PCINT1)_37") (pintype "bidirectional"))
    )
    (net (code "58") (name "SERIAL0_RX") (class "Default")
      (node (ref "JP3") (pin "RXI") (pinfunction "2_RXI") (pintype "passive"))
      (node (ref "U2") (pin "46") (pinfunction "PE0(RXD0/PCINT8)_46") (pintype "bidirectional"))
    )
    (net (code "59") (name "SERIAL0_TX") (class "Default")
      (node (ref "JP3") (pin "TXO") (pinfunction "3_TXO") (pintype "passive"))
      (node (ref "U2") (pin "47") (pinfunction "PE1(TXD0)_47") (pintype "bidirectional"))
    )
    (net (code "60") (name "VCC") (class "Default")
      (node (ref "C21") (pin "+") (pinfunction "+_+") (pintype "passive"))
      (node (ref "JP5") (pin "2") (pinfunction "2_2") (pintype "passive"))
      (node (ref "R1") (pin "1") (pinfunction "CCW_1") (pintype "passive"))
      (node (ref "R17") (pin "P$2") (pinfunction "2_P$2") (pintype "passive"))
      (node (ref "U$7") (pin "1") (pinfunction "VI_1") (pintype "input"))
    )
    (net (code "61") (name "VCUTOFF") (class "Default")
      (node (ref "JP2") (pin "1") (pinfunction "1_1") (pintype "passive"))
      (node (ref "R1") (pin "2") (pinfunction "WIPER_2") (pintype "passive"))
      (node (ref "U$5") (pin "1") (pinfunction "R_1") (pintype "bidirectional"))
    )
    (net (code "62") (name "XTAL1_16MHZ") (class "Default")
      (node (ref "C17") (pin "1") (pinfunction "1_1") (pintype "passive"))
      (node (ref "U2") (pin "57") (pinfunction "XTAL1_57") (pintype "bidirectional"))
      (node (ref "Y2") (pin "1") (pinfunction "1_1") (pintype "passive"))
    )
    (net (code "63") (name "XTAL1_RTC") (class "Default")
      (node (ref "C16") (pin "1") (pinfunction "1_1") (pintype "passive"))
      (node (ref "U2") (pin "18") (pinfunction "PG4(TOSC1)_18") (pintype "bidirectional"))
      (node (ref "Y1") (pin "X1") (pinfunction "1_X1") (pintype "passive"))
    )
    (net (code "64") (name "XTAL2_16MHZ") (class "Default")
      (node (ref "C20") (pin "1") (pinfunction "1_1") (pintype "passive"))
      (node (ref "U2") (pin "56") (pinfunction "XTAL2_56") (pintype "bidirectional"))
      (node (ref "Y2") (pin "3") (pinfunction "2_3") (pintype "passive"))
    )
    (net (code "65") (name "XTAL2_RTC") (class "Default")
      (node (ref "C19") (pin "1") (pinfunction "1_1") (pintype "passive"))
      (node (ref "U2") (pin "17") (pinfunction "PG3(TOSC2)_17") (pintype "bidirectional"))
      (node (ref "Y1") (pin "X2") (pinfunction "2_X2") (pintype "passive"))
    )
    (net (code "66") (name "unconnected-(JP3-5-PadCTS)") (class "Default")
      (node (ref "JP3") (pin "CTS") (pinfunction "5_CTS") (pintype "passive"))
    )
    (net (code "67") (name "unconnected-(U$2-P1-PadP2)") (class "Default")
      (node (ref "U$2") (pin "P2") (pinfunction "P1_P2") (pintype "passive"))
    )
    (net (code "68") (name "unconnected-(U$2-S1-PadS2)") (class "Default")
      (node (ref "U$2") (pin "S2") (pinfunction "S1_S2") (pintype "passive"))
    )
    (net (code "69") (name "unconnected-(U$4-P1-PadP2)") (class "Default")
      (node (ref "U$4") (pin "P2") (pinfunction "P1_P2") (pintype "passive"))
    )
    (net (code "70") (name "unconnected-(U$4-S1-PadS2)") (class "Default")
      (node (ref "U$4") (pin "S2") (pinfunction "S1_S2") (pintype "passive"))
    )
    (net (code "71") (name "unconnected-(U$6-P1-PadP2)") (class "Default")
      (node (ref "U$6") (pin "P2") (pinfunction "P1_P2") (pintype "passive"))
    )
    (net (code "72") (name "unconnected-(U$6-S1-PadS2)") (class "Default")
      (node (ref "U$6") (pin "S2") (pinfunction "S1_S2") (pintype "passive"))
    )
    (net (code "73") (name "unconnected-(U$8-P1-PadP2)") (class "Default")
      (node (ref "U$8") (pin "P2") (pinfunction "P1_P2") (pintype "passive"))
    )
    (net (code "74") (name "unconnected-(U$8-S1-PadS2)") (class "Default")
      (node (ref "U$8") (pin "S2") (pinfunction "S1_S2") (pintype "passive"))
    )
    (net (code "75") (name "unconnected-(U$10-P1-PadP2)") (class "Default")
      (node (ref "U$10") (pin "P2") (pinfunction "P1_P2") (pintype "passive"))
    )
    (net (code "76") (name "unconnected-(U$10-S1-PadS2)") (class "Default")
      (node (ref "U$10") (pin "S2") (pinfunction "S1_S2") (pintype "passive"))
    )
    (net (code "77") (name "unconnected-(U$11-P1-PadP2)") (class "Default")
      (node (ref "U$11") (pin "P2") (pinfunction "P1_P2") (pintype "passive"))
    )
    (net (code "78") (name "unconnected-(U$11-S1-PadS2)") (class "Default")
      (node (ref "U$11") (pin "S2") (pinfunction "S1_S2") (pintype "passive"))
    )
    (net (code "79") (name "unconnected-(U$12-P1-PadP2)") (class "Default")
      (node (ref "U$12") (pin "P2") (pinfunction "P1_P2") (pintype "passive"))
    )
    (net (code "80") (name "unconnected-(U$12-S1-PadS2)") (class "Default")
      (node (ref "U$12") (pin "S2") (pinfunction "S1_S2") (pintype "passive"))
    )
    (net (code "81") (name "unconnected-(U$13-P1-PadP2)") (class "Default")
      (node (ref "U$13") (pin "P2") (pinfunction "P1_P2") (pintype "passive"))
    )
    (net (code "82") (name "unconnected-(U$13-S1-PadS2)") (class "Default")
      (node (ref "U$13") (pin "S2") (pinfunction "S1_S2") (pintype "passive"))
    )
  )
)
